# BottleBuddy.net
KiCad netlist of a schematic drawn in EAGLE
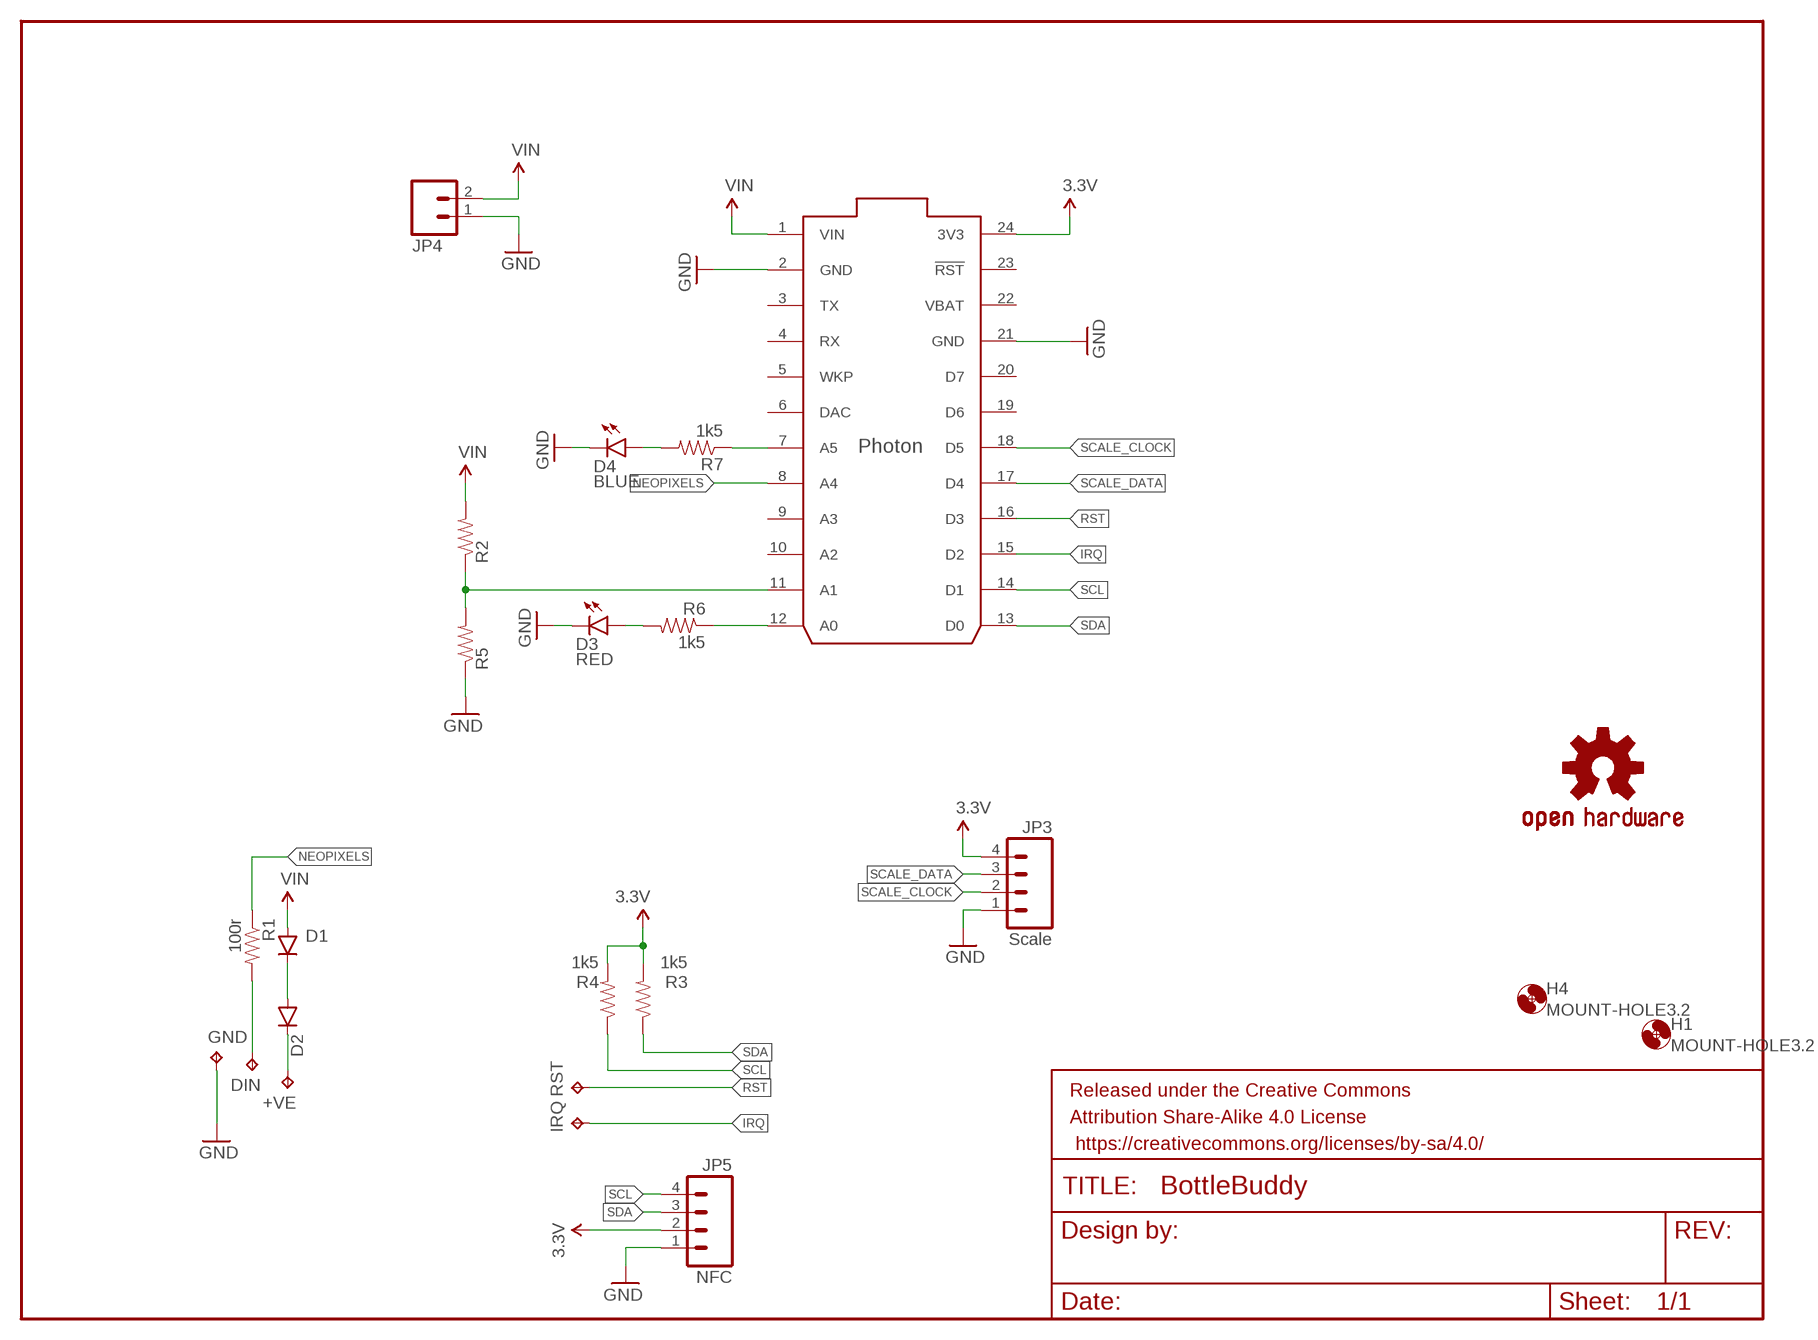
[diagram p0: schematic, sheet 1]

(export (version "E")
  (design (tool "Eeschema 10.0.6"))
  (components
    (comp (ref "+VE")
      (value "TPTP20R")
      (footprint "eagle-import:TP20R")
      (libsource (lib "eagle-import") (part "TPTP20R"))
    )
    (comp (ref "D1")
      (value "DIODESMA")
      (footprint "eagle-import:SMA-DIODE")
      (libsource (lib "eagle-import") (part "DIODESMA"))
    )
    (comp (ref "D2")
      (value "DIODESMA")
      (footprint "eagle-import:SMA-DIODE")
      (libsource (lib "eagle-import") (part "DIODESMA"))
    )
    (comp (ref "D3")
      (value "RED")
      (footprint "eagle-import:LED-1206")
      (libsource (lib "eagle-import") (part "LED1206"))
    )
    (comp (ref "D4")
      (value "BLUE")
      (footprint "eagle-import:LED-1206")
      (libsource (lib "eagle-import") (part "LED1206"))
    )
    (comp (ref "DIN")
      (value "TPTP20R")
      (footprint "eagle-import:TP20R")
      (libsource (lib "eagle-import") (part "TPTP20R"))
    )
    (comp (ref "FRAME1")
      (value "FRAME-LETTER")
      (footprint "eagle-import:CREATIVE_COMMONS")
      (libsource (lib "eagle-import") (part "FRAME-LETTER"))
    )
    (comp (ref "GND")
      (value "TPTP20R")
      (footprint "eagle-import:TP20R")
      (libsource (lib "eagle-import") (part "TPTP20R"))
    )
    (comp (ref "H1")
      (value "MOUNT-HOLE3.2")
      (footprint "eagle-import:3,2")
      (libsource (lib "eagle-import") (part "MOUNT-HOLE3.2"))
    )
    (comp (ref "H4")
      (value "MOUNT-HOLE3.2")
      (footprint "eagle-import:3,2")
      (libsource (lib "eagle-import") (part "MOUNT-HOLE3.2"))
    )
    (comp (ref "IRQ")
      (value "NFC IRQ")
      (footprint "eagle-import:TP20R")
      (libsource (lib "eagle-import") (part "TPTP20R"))
    )
    (comp (ref "JP3")
      (value "Scale")
      (footprint "eagle-import:1X04")
      (libsource (lib "eagle-import") (part "M04PTH"))
    )
    (comp (ref "JP4")
      (value "M02-JST-2MM-SMT")
      (footprint "eagle-import:JST-2-SMD")
      (libsource (lib "eagle-import") (part "M02-JST-2MM-SMT"))
    )
    (comp (ref "JP5")
      (value "NFC")
      (footprint "eagle-import:1X04")
      (libsource (lib "eagle-import") (part "M04PTH"))
    )
    (comp (ref "LOGO2")
      (value "OSHW-LOGOL")
      (footprint "eagle-import:OSHW-LOGO-L")
      (libsource (lib "eagle-import") (part "OSHW-LOGOL"))
    )
    (comp (ref "R1")
      (value "100r")
      (footprint "eagle-import:1206")
      (libsource (lib "eagle-import") (part "RESISTOR1206"))
    )
    (comp (ref "R2")
      (value "RESISTOR1206")
      (footprint "eagle-import:1206")
      (libsource (lib "eagle-import") (part "RESISTOR1206"))
    )
    (comp (ref "R3")
      (value "1k5")
      (footprint "eagle-import:1206")
      (libsource (lib "eagle-import") (part "RESISTOR1206"))
    )
    (comp (ref "R4")
      (value "1k5")
      (footprint "eagle-import:1206")
      (libsource (lib "eagle-import") (part "RESISTOR1206"))
    )
    (comp (ref "R5")
      (value "RESISTOR1206")
      (footprint "eagle-import:1206")
      (libsource (lib "eagle-import") (part "RESISTOR1206"))
    )
    (comp (ref "R6")
      (value "1k5")
      (footprint "eagle-import:1206")
      (libsource (lib "eagle-import") (part "RESISTOR1206"))
    )
    (comp (ref "R7")
      (value "1k5")
      (footprint "eagle-import:1206")
      (libsource (lib "eagle-import") (part "RESISTOR1206"))
    )
    (comp (ref "RST")
      (value "TPTP20R")
      (footprint "eagle-import:TP20R")
      (libsource (lib "eagle-import") (part "TPTP20R"))
    )
    (comp (ref "U$1")
      (value "PHOTON_WITH_HEADERS")
      (footprint "eagle-import:PHOTON")
      (libsource (lib "eagle-import") (part "PHOTON_WITH_HEADERS"))
    )
  )
  (nets
    (net (code "1") (name "/VBAT") (class "Default")
      (node (ref "U$1") (pin "22") (pinfunction "VBAT_22") (pintype "power_in"))
    )
    (net (code "2") (name "3.3V") (class "Default")
      (node (ref "JP3") (pin "4") (pinfunction "4_4") (pintype "passive"))
      (node (ref "JP5") (pin "2") (pinfunction "2_2") (pintype "passive"))
      (node (ref "R3") (pin "2") (pinfunction "2_2") (pintype "passive"))
      (node (ref "R4") (pin "2") (pinfunction "2_2") (pintype "passive"))
      (node (ref "U$1") (pin "24") (pinfunction "3V3_24") (pintype "power_in"))
    )
    (net (code "3") (name "GND") (class "Default")
      (node (ref "D3") (pin "C") (pinfunction "C_C") (pintype "passive"))
      (node (ref "D4") (pin "C") (pinfunction "C_C") (pintype "passive"))
      (node (ref "GND") (pin "TP") (pinfunction "TP_TP") (pintype "input"))
      (node (ref "JP3") (pin "1") (pinfunction "1_1") (pintype "passive"))
      (node (ref "JP4") (pin "1") (pinfunction "2_1") (pintype "passive"))
      (node (ref "JP5") (pin "1") (pinfunction "1_1") (pintype "passive"))
      (node (ref "R5") (pin "1") (pinfunction "1_1") (pintype "passive"))
      (node (ref "U$1") (pin "2") (pinfunction "GND_2") (pintype "power_in"))
      (node (ref "U$1") (pin "21") (pinfunction "GND_21") (pintype "power_in"))
    )
    (net (code "4") (name "IRQ") (class "Default")
      (node (ref "IRQ") (pin "TP") (pinfunction "TP_TP") (pintype "input"))
      (node (ref "U$1") (pin "15") (pinfunction "D2_15") (pintype "bidirectional"))
    )
    (net (code "5") (name "NEOPIXELS") (class "Default")
      (node (ref "R1") (pin "1") (pinfunction "1_1") (pintype "passive"))
      (node (ref "U$1") (pin "8") (pinfunction "A4_8") (pintype "bidirectional"))
    )
    (net (code "6") (name "Net-(+VE-PadTP)") (class "Default")
      (node (ref "+VE") (pin "TP") (pinfunction "TP_TP") (pintype "input"))
      (node (ref "D2") (pin "C") (pinfunction "C_C") (pintype "passive"))
    )
    (net (code "7") (name "Net-(D1-PadC)") (class "Default")
      (node (ref "D1") (pin "C") (pinfunction "C_C") (pintype "passive"))
      (node (ref "D2") (pin "A") (pinfunction "A_A") (pintype "passive"))
    )
    (net (code "8") (name "Net-(D3-PadA)") (class "Default")
      (node (ref "D3") (pin "A") (pinfunction "A_A") (pintype "passive"))
      (node (ref "R6") (pin "2") (pinfunction "2_2") (pintype "passive"))
    )
    (net (code "9") (name "Net-(D4-PadA)") (class "Default")
      (node (ref "D4") (pin "A") (pinfunction "A_A") (pintype "passive"))
      (node (ref "R7") (pin "2") (pinfunction "2_2") (pintype "passive"))
    )
    (net (code "10") (name "Net-(DIN-PadTP)") (class "Default")
      (node (ref "DIN") (pin "TP") (pinfunction "TP_TP") (pintype "input"))
      (node (ref "R1") (pin "2") (pinfunction "2_2") (pintype "passive"))
    )
    (net (code "11") (name "Net-(U$1-A0)") (class "Default")
      (node (ref "R6") (pin "1") (pinfunction "1_1") (pintype "passive"))
      (node (ref "U$1") (pin "12") (pinfunction "A0_12") (pintype "bidirectional"))
    )
    (net (code "12") (name "Net-(U$1-A1)") (class "Default")
      (node (ref "R2") (pin "1") (pinfunction "1_1") (pintype "passive"))
      (node (ref "R5") (pin "2") (pinfunction "2_2") (pintype "passive"))
      (node (ref "U$1") (pin "11") (pinfunction "A1_11") (pintype "bidirectional"))
    )
    (net (code "13") (name "Net-(U$1-A5)") (class "Default")
      (node (ref "R7") (pin "1") (pinfunction "1_1") (pintype "passive"))
      (node (ref "U$1") (pin "7") (pinfunction "A5_7") (pintype "bidirectional"))
    )
    (net (code "14") (name "RST") (class "Default")
      (node (ref "RST") (pin "TP") (pinfunction "TP_TP") (pintype "input"))
      (node (ref "U$1") (pin "16") (pinfunction "D3_16") (pintype "bidirectional"))
    )
    (net (code "15") (name "SCALE_CLOCK") (class "Default")
      (node (ref "JP3") (pin "2") (pinfunction "2_2") (pintype "passive"))
      (node (ref "U$1") (pin "18") (pinfunction "D5_18") (pintype "bidirectional"))
    )
    (net (code "16") (name "SCALE_DATA") (class "Default")
      (node (ref "JP3") (pin "3") (pinfunction "3_3") (pintype "passive"))
      (node (ref "U$1") (pin "17") (pinfunction "D4_17") (pintype "bidirectional"))
    )
    (net (code "17") (name "SCL") (class "Default")
      (node (ref "JP5") (pin "4") (pinfunction "4_4") (pintype "passive"))
      (node (ref "R4") (pin "1") (pinfunction "1_1") (pintype "passive"))
      (node (ref "U$1") (pin "14") (pinfunction "D1_14") (pintype "bidirectional"))
    )
    (net (code "18") (name "SDA") (class "Default")
      (node (ref "JP5") (pin "3") (pinfunction "3_3") (pintype "passive"))
      (node (ref "R3") (pin "1") (pinfunction "1_1") (pintype "passive"))
      (node (ref "U$1") (pin "13") (pinfunction "D0_13") (pintype "bidirectional"))
    )
    (net (code "19") (name "VIN") (class "Default")
      (node (ref "D1") (pin "A") (pinfunction "A_A") (pintype "passive"))
      (node (ref "JP4") (pin "2") (pinfunction "1_2") (pintype "passive"))
      (node (ref "R2") (pin "2") (pinfunction "2_2") (pintype "passive"))
      (node (ref "U$1") (pin "1") (pinfunction "VIN_1") (pintype "power_in"))
    )
    (net (code "20") (name "unconnected-(U$1-A2-Pad10)") (class "Default")
      (node (ref "U$1") (pin "10") (pinfunction "A2_10") (pintype "bidirectional"))
    )
    (net (code "21") (name "unconnected-(U$1-A3-Pad9)") (class "Default")
      (node (ref "U$1") (pin "9") (pinfunction "A3_9") (pintype "bidirectional"))
    )
    (net (code "22") (name "unconnected-(U$1-D6-Pad19)") (class "Default")
      (node (ref "U$1") (pin "19") (pinfunction "D6_19") (pintype "bidirectional"))
    )
    (net (code "23") (name "unconnected-(U$1-D7-Pad20)") (class "Default")
      (node (ref "U$1") (pin "20") (pinfunction "D7_20") (pintype "bidirectional"))
    )
    (net (code "24") (name "unconnected-(U$1-DAC-Pad6)") (class "Default")
      (node (ref "U$1") (pin "6") (pinfunction "DAC_6") (pintype "bidirectional"))
    )
    (net (code "25") (name "unconnected-(U$1-RX-Pad4)") (class "Default")
      (node (ref "U$1") (pin "4") (pinfunction "RX_4") (pintype "bidirectional"))
    )
    (net (code "26") (name "unconnected-(U$1-TX-Pad3)") (class "Default")
      (node (ref "U$1") (pin "3") (pinfunction "TX_3") (pintype "bidirectional"))
    )
    (net (code "27") (name "unconnected-(U$1-WKP-Pad5)") (class "Default")
      (node (ref "U$1") (pin "5") (pinfunction "WKP_5") (pintype "bidirectional"))
    )
    (net (code "28") (name "unconnected-(U$1-~{RST}-Pad23)") (class "Default")
      (node (ref "U$1") (pin "23") (pinfunction "~{RST}_23") (pintype "bidirectional"))
    )
  )
)
